# DDS_Tone_Shield.net
KiCad netlist of a schematic drawn in EAGLE
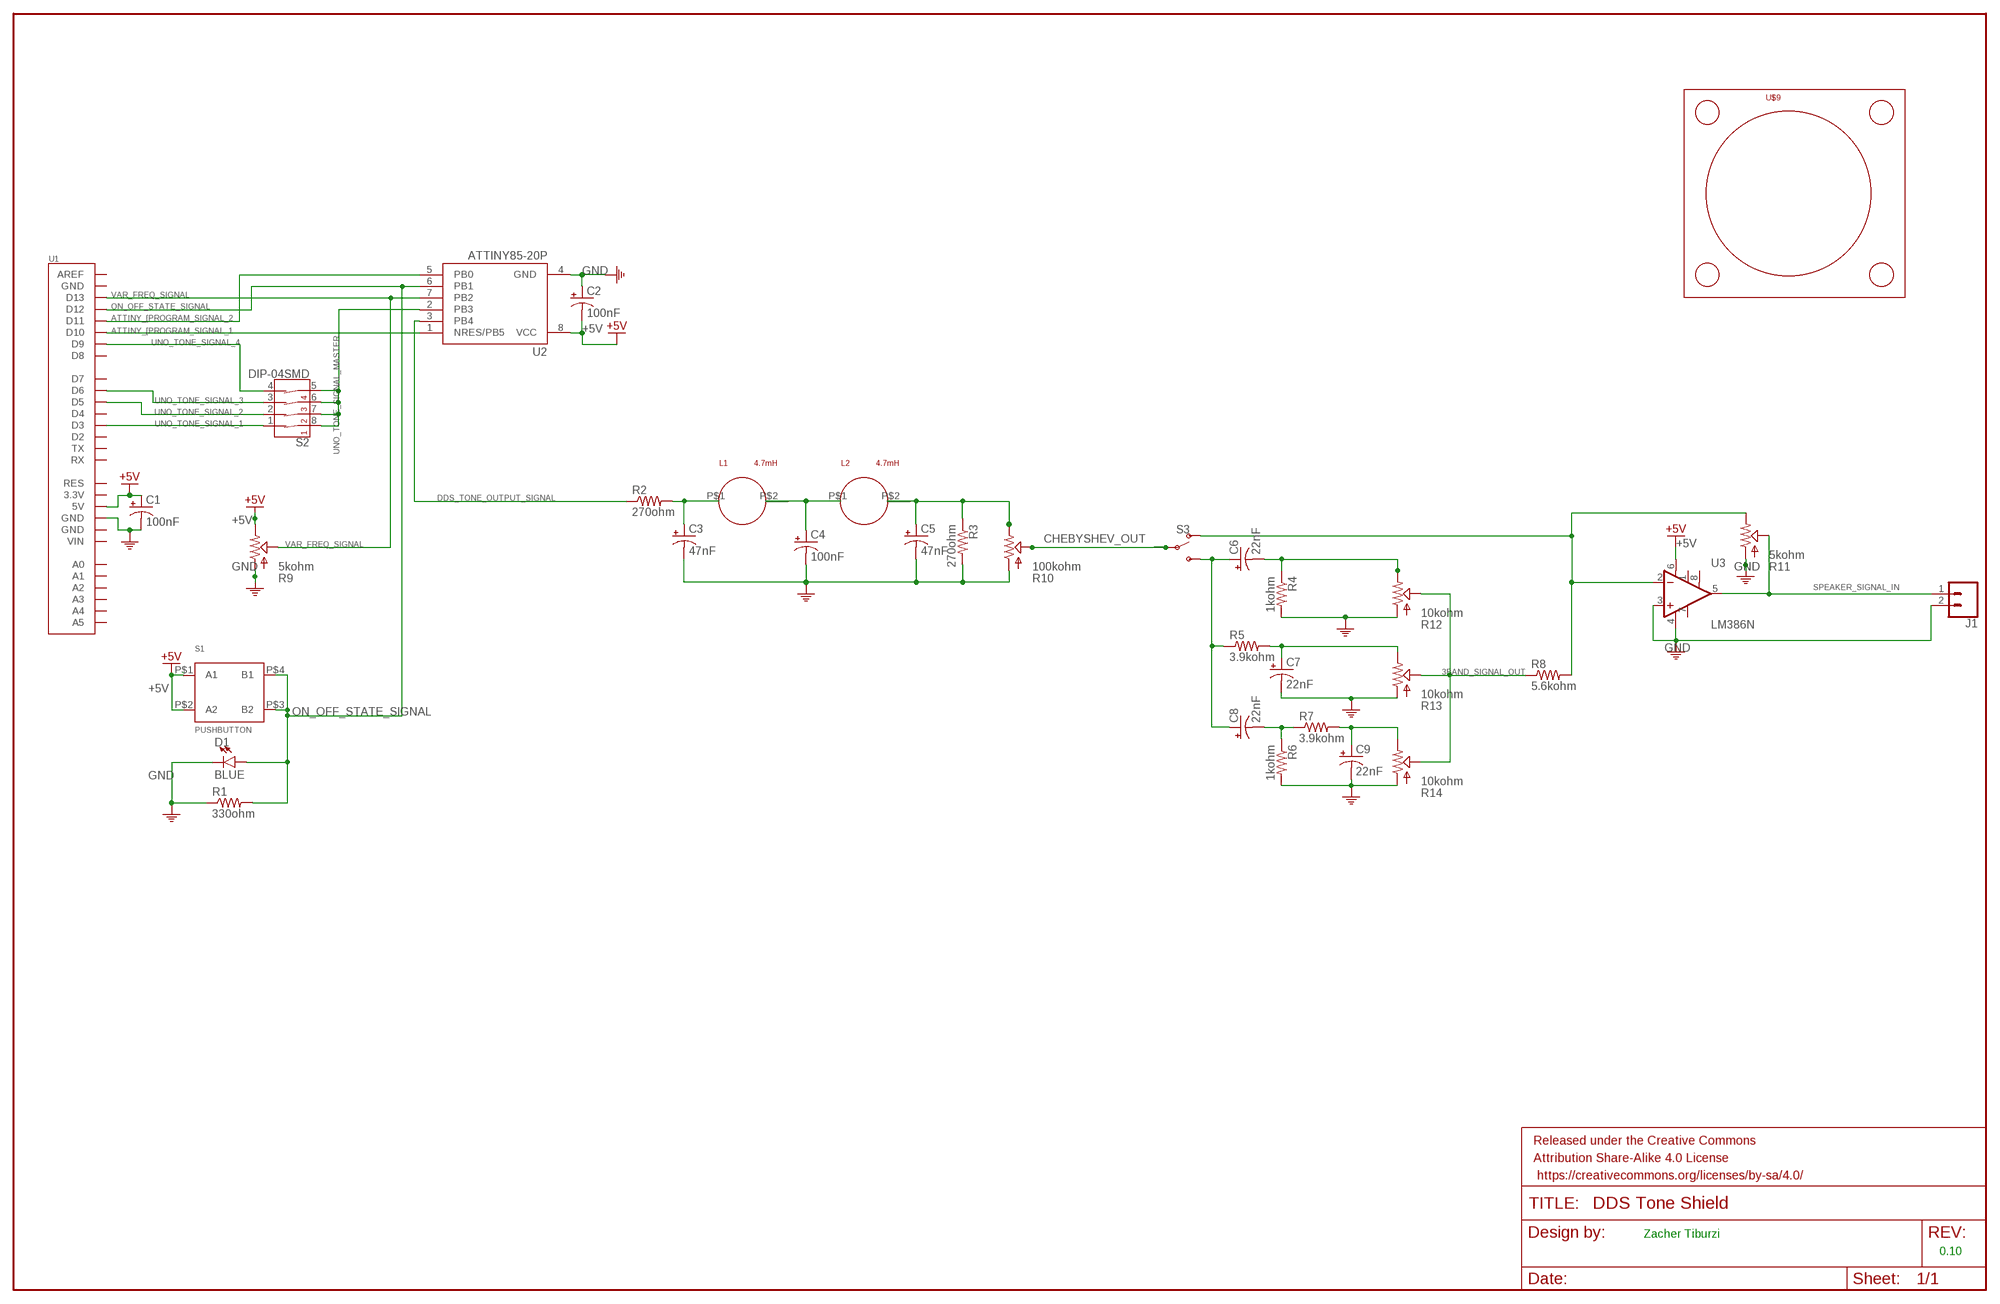
[diagram p0: schematic, sheet 1]

(export (version "E")
  (design (tool "Eeschema 10.0.6"))
  (components
    (comp (ref "C1")
      (value "100nF")
      (footprint "eagle-import:EIA3216")
      (libsource (lib "eagle-import") (part "CAP_POL1206"))
    )
    (comp (ref "C2")
      (value "100nF")
      (footprint "eagle-import:EIA3216")
      (libsource (lib "eagle-import") (part "CAP_POL1206"))
    )
    (comp (ref "C3")
      (value "47nF")
      (footprint "eagle-import:EIA3216")
      (libsource (lib "eagle-import") (part "CAP_POL1206"))
    )
    (comp (ref "C4")
      (value "100nF")
      (footprint "eagle-import:EIA3216")
      (libsource (lib "eagle-import") (part "CAP_POL1206"))
    )
    (comp (ref "C5")
      (value "47nF")
      (footprint "eagle-import:EIA3216")
      (libsource (lib "eagle-import") (part "CAP_POL1206"))
    )
    (comp (ref "C6")
      (value "22nF")
      (footprint "eagle-import:EIA3216")
      (libsource (lib "eagle-import") (part "CAP_POL1206"))
    )
    (comp (ref "C7")
      (value "22nF")
      (footprint "eagle-import:EIA3216")
      (libsource (lib "eagle-import") (part "CAP_POL1206"))
    )
    (comp (ref "C8")
      (value "22nF")
      (footprint "eagle-import:EIA3216")
      (libsource (lib "eagle-import") (part "CAP_POL1206"))
    )
    (comp (ref "C9")
      (value "22nF")
      (footprint "eagle-import:EIA3216")
      (libsource (lib "eagle-import") (part "CAP_POL1206"))
    )
    (comp (ref "D1")
      (value "BLUE")
      (footprint "eagle-import:LED-1206")
      (libsource (lib "eagle-import") (part "LED-BLUE1206"))
    )
    (comp (ref "FRAME2")
      (value "FRAME-LEDGER")
      (footprint "eagle-import:CREATIVE_COMMONS")
      (libsource (lib "eagle-import") (part "FRAME-LEDGER"))
    )
    (comp (ref "J1")
      (value "CONN_02")
      (footprint "eagle-import:1X02")
      (libsource (lib "eagle-import") (part "CONN_02"))
    )
    (comp (ref "L1")
      (value "4.7mH")
      (footprint "eagle-import:SDR0503-472JL")
      (libsource (lib "eagle-import") (part "INDUCTOR"))
    )
    (comp (ref "L2")
      (value "4.7mH")
      (footprint "eagle-import:SDR0503-472JL")
      (libsource (lib "eagle-import") (part "INDUCTOR"))
    )
    (comp (ref "R1")
      (value "330ohm")
      (footprint "eagle-import:1206")
      (libsource (lib "eagle-import") (part "RESISTOR1206"))
    )
    (comp (ref "R2")
      (value "270ohm")
      (footprint "eagle-import:1206")
      (libsource (lib "eagle-import") (part "RESISTOR1206"))
    )
    (comp (ref "R3")
      (value "270ohm")
      (footprint "eagle-import:1206")
      (libsource (lib "eagle-import") (part "RESISTOR1206"))
    )
    (comp (ref "R4")
      (value "1kohm")
      (footprint "eagle-import:1206")
      (libsource (lib "eagle-import") (part "RESISTOR1206"))
    )
    (comp (ref "R5")
      (value "3.9kohm")
      (footprint "eagle-import:1206")
      (libsource (lib "eagle-import") (part "RESISTOR1206"))
    )
    (comp (ref "R6")
      (value "1kohm")
      (footprint "eagle-import:1206")
      (libsource (lib "eagle-import") (part "RESISTOR1206"))
    )
    (comp (ref "R7")
      (value "3.9kohm")
      (footprint "eagle-import:1206")
      (libsource (lib "eagle-import") (part "RESISTOR1206"))
    )
    (comp (ref "R8")
      (value "5.6kohm")
      (footprint "eagle-import:1206")
      (libsource (lib "eagle-import") (part "RESISTOR1206"))
    )
    (comp (ref "R9")
      (value "5kohm")
      (footprint "eagle-import:RK09K_RK09D_SERIES")
      (libsource (lib "eagle-import") (part "POT1"))
    )
    (comp (ref "R10")
      (value "100kohm")
      (footprint "eagle-import:5150500311")
      (libsource (lib "eagle-import") (part "POT2"))
    )
    (comp (ref "R11")
      (value "5kohm")
      (footprint "eagle-import:RK09K_RK09D_SERIES")
      (libsource (lib "eagle-import") (part "POT1"))
    )
    (comp (ref "R12")
      (value "10kohm")
      (footprint "eagle-import:RK09K_RK09D_SERIES")
      (libsource (lib "eagle-import") (part "POT1"))
    )
    (comp (ref "R13")
      (value "10kohm")
      (footprint "eagle-import:RK09K_RK09D_SERIES")
      (libsource (lib "eagle-import") (part "POT1"))
    )
    (comp (ref "R14")
      (value "10kohm")
      (footprint "eagle-import:RK09K_RK09D_SERIES")
      (libsource (lib "eagle-import") (part "POT1"))
    )
    (comp (ref "S1")
      (value "PUSHBUTTON")
      (footprint "eagle-import:3CSH9_MEC_PUSHBUTTON")
      (libsource (lib "eagle-import") (part "PUSHBUTTON"))
    )
    (comp (ref "S2")
      (value "DIP-04SMD")
      (footprint "eagle-import:DIPSWITCH-04-SMD")
      (libsource (lib "eagle-import") (part "DIP-04SMD"))
    )
    (comp (ref "S3")
      (value "SWITCH-SPDT")
      (footprint "eagle-import:JS102011SAQN")
      (libsource (lib "eagle-import") (part "SWITCH-SPDT"))
    )
    (comp (ref "U$9")
      (value "SPEAKER")
      (footprint "eagle-import:CSS-40408N")
      (libsource (lib "eagle-import") (part "SPEAKER"))
    )
    (comp (ref "U1")
      (value "ARDUINO_SHIELD")
      (footprint "eagle-import:DUEMILANOVE_SHIELD")
      (libsource (lib "eagle-import") (part "ARDUINO_SHIELD"))
    )
    (comp (ref "U2")
      (value "ATTINY85-20P")
      (footprint "eagle-import:PDIP08_300MIL")
      (libsource (lib "eagle-import") (part "ATTINY85P-20"))
    )
    (comp (ref "U3")
      (value "LM386N")
      (footprint "eagle-import:DIP08")
      (libsource (lib "eagle-import") (part "LM386"))
    )
  )
  (nets
    (net (code "1") (name "+5V") (class "Default")
      (node (ref "C1") (pin "A") (pinfunction "+_A") (pintype "passive"))
      (node (ref "C2") (pin "C") (pinfunction "-_C") (pintype "passive"))
      (node (ref "R9") (pin "P$3") (pinfunction "E_P$3") (pintype "passive"))
      (node (ref "S1") (pin "P$1") (pinfunction "A1_P$1") (pintype "bidirectional"))
      (node (ref "S1") (pin "P$2") (pinfunction "A2_P$2") (pintype "bidirectional"))
      (node (ref "U1") (pin "5V") (pinfunction "5V_5V") (pintype "bidirectional"))
      (node (ref "U2") (pin "8") (pinfunction "VCC_8") (pintype "power_in"))
      (node (ref "U3") (pin "6") (pinfunction "V+_6") (pintype "power_in"))
    )
    (net (code "2") (name "/3BAND_SIGNAL_OUT") (class "Default")
      (node (ref "R12") (pin "P$2") (pinfunction "S_P$2") (pintype "passive"))
      (node (ref "R13") (pin "P$2") (pinfunction "S_P$2") (pintype "passive"))
      (node (ref "R14") (pin "P$2") (pinfunction "S_P$2") (pintype "passive"))
      (node (ref "R8") (pin "1") (pinfunction "1_1") (pintype "passive"))
    )
    (net (code "3") (name "/ATTINY_[PROGRAM_SIGNAL_1") (class "Default")
      (node (ref "U1") (pin "D10") (pinfunction "D10_D10") (pintype "bidirectional"))
      (node (ref "U2") (pin "1") (pinfunction "NRES/PB5_1") (pintype "bidirectional"))
    )
    (net (code "4") (name "/ATTINY_[PROGRAM_SIGNAL_2") (class "Default")
      (node (ref "U1") (pin "D11") (pinfunction "D11_D11") (pintype "bidirectional"))
      (node (ref "U2") (pin "5") (pinfunction "PB0_5") (pintype "bidirectional"))
    )
    (net (code "5") (name "/CHEBYSHEV_OUT") (class "Default")
      (node (ref "R10") (pin "P$20") (pinfunction "S_P$20") (pintype "passive"))
      (node (ref "S3") (pin "P$3") (pinfunction "P_P$3") (pintype "passive"))
    )
    (net (code "6") (name "/DDS_TONE_OUTPUT_SIGNAL") (class "Default")
      (node (ref "R2") (pin "1") (pinfunction "1_1") (pintype "passive"))
      (node (ref "U2") (pin "3") (pinfunction "PB4_3") (pintype "bidirectional"))
    )
    (net (code "7") (name "/ON_OFF_STATE_SIGNAL") (class "Default")
      (node (ref "D1") (pin "A") (pinfunction "A_A") (pintype "passive"))
      (node (ref "R1") (pin "2") (pinfunction "2_2") (pintype "passive"))
      (node (ref "S1") (pin "P$3") (pinfunction "B2_P$3") (pintype "bidirectional"))
      (node (ref "S1") (pin "P$4") (pinfunction "B1_P$4") (pintype "bidirectional"))
      (node (ref "U1") (pin "D12") (pinfunction "D12_D12") (pintype "bidirectional"))
      (node (ref "U2") (pin "6") (pinfunction "PB1_6") (pintype "bidirectional"))
    )
    (net (code "8") (name "/SPEAKER_SIGNAL_IN") (class "Default")
      (node (ref "J1") (pin "1") (pinfunction "1_1") (pintype "passive"))
      (node (ref "R11") (pin "P$2") (pinfunction "S_P$2") (pintype "passive"))
      (node (ref "U3") (pin "5") (pinfunction "OUT_5") (pintype "output"))
    )
    (net (code "9") (name "/UNO_TONE_SIGNAL_1") (class "Default")
      (node (ref "S2") (pin "1") (pinfunction "1A_1") (pintype "bidirectional"))
      (node (ref "U1") (pin "D3") (pinfunction "D3_D3") (pintype "bidirectional"))
    )
    (net (code "10") (name "/UNO_TONE_SIGNAL_2") (class "Default")
      (node (ref "S2") (pin "2") (pinfunction "2A_2") (pintype "bidirectional"))
      (node (ref "U1") (pin "D5") (pinfunction "D5_D5") (pintype "bidirectional"))
    )
    (net (code "11") (name "/UNO_TONE_SIGNAL_3") (class "Default")
      (node (ref "S2") (pin "3") (pinfunction "3A_3") (pintype "bidirectional"))
      (node (ref "U1") (pin "D6") (pinfunction "D6_D6") (pintype "bidirectional"))
    )
    (net (code "12") (name "/UNO_TONE_SIGNAL_4") (class "Default")
      (node (ref "S2") (pin "4") (pinfunction "4A_4") (pintype "bidirectional"))
      (node (ref "U1") (pin "D9") (pinfunction "D9_D9") (pintype "bidirectional"))
    )
    (net (code "13") (name "/UNO_TONE_SIGNAL_MASTER") (class "Default")
      (node (ref "S2") (pin "5") (pinfunction "4B_5") (pintype "bidirectional"))
      (node (ref "S2") (pin "6") (pinfunction "3B_6") (pintype "bidirectional"))
      (node (ref "S2") (pin "7") (pinfunction "2B_7") (pintype "bidirectional"))
      (node (ref "S2") (pin "8") (pinfunction "1B_8") (pintype "bidirectional"))
      (node (ref "U2") (pin "2") (pinfunction "PB3_2") (pintype "bidirectional"))
    )
    (net (code "14") (name "/VAR_FREQ_SIGNAL") (class "Default")
      (node (ref "R9") (pin "P$2") (pinfunction "S_P$2") (pintype "passive"))
      (node (ref "U1") (pin "D13") (pinfunction "D13_D13") (pintype "bidirectional"))
      (node (ref "U2") (pin "7") (pinfunction "PB2_7") (pintype "bidirectional"))
    )
    (net (code "15") (name "GND_US") (class "Default")
      (node (ref "C1") (pin "C") (pinfunction "-_C") (pintype "passive"))
      (node (ref "C2") (pin "A") (pinfunction "+_A") (pintype "passive"))
      (node (ref "C3") (pin "C") (pinfunction "-_C") (pintype "passive"))
      (node (ref "C4") (pin "C") (pinfunction "-_C") (pintype "passive"))
      (node (ref "C5") (pin "C") (pinfunction "-_C") (pintype "passive"))
      (node (ref "C7") (pin "C") (pinfunction "-_C") (pintype "passive"))
      (node (ref "C9") (pin "C") (pinfunction "-_C") (pintype "passive"))
      (node (ref "D1") (pin "C") (pinfunction "C_C") (pintype "passive"))
      (node (ref "J1") (pin "2") (pinfunction "2_2") (pintype "passive"))
      (node (ref "R1") (pin "1") (pinfunction "1_1") (pintype "passive"))
      (node (ref "R10") (pin "P$10") (pinfunction "A_P$10") (pintype "passive"))
      (node (ref "R11") (pin "P$1") (pinfunction "A_P$1") (pintype "passive"))
      (node (ref "R12") (pin "P$1") (pinfunction "A_P$1") (pintype "passive"))
      (node (ref "R13") (pin "P$1") (pinfunction "A_P$1") (pintype "passive"))
      (node (ref "R14") (pin "P$1") (pinfunction "A_P$1") (pintype "passive"))
      (node (ref "R3") (pin "2") (pinfunction "2_2") (pintype "passive"))
      (node (ref "R4") (pin "2") (pinfunction "2_2") (pintype "passive"))
      (node (ref "R6") (pin "2") (pinfunction "2_2") (pintype "passive"))
      (node (ref "R9") (pin "P$1") (pinfunction "A_P$1") (pintype "passive"))
      (node (ref "U1") (pin "GND@1") (pinfunction "GND_GND@1") (pintype "bidirectional"))
      (node (ref "U2") (pin "4") (pinfunction "GND_4") (pintype "power_in"))
      (node (ref "U3") (pin "3") (pinfunction "+IN_3") (pintype "input"))
      (node (ref "U3") (pin "4") (pinfunction "V-_4") (pintype "power_in"))
    )
    (net (code "16") (name "Net-(C3-+)") (class "Default")
      (node (ref "C3") (pin "A") (pinfunction "+_A") (pintype "passive"))
      (node (ref "L1") (pin "P$1") (pinfunction "P$1_P$1") (pintype "bidirectional"))
      (node (ref "R2") (pin "2") (pinfunction "2_2") (pintype "passive"))
    )
    (net (code "17") (name "Net-(C4-+)") (class "Default")
      (node (ref "C4") (pin "A") (pinfunction "+_A") (pintype "passive"))
      (node (ref "L1") (pin "P$2") (pinfunction "P$2_P$2") (pintype "bidirectional"))
      (node (ref "L2") (pin "P$1") (pinfunction "P$1_P$1") (pintype "bidirectional"))
    )
    (net (code "18") (name "Net-(C5-+)") (class "Default")
      (node (ref "C5") (pin "A") (pinfunction "+_A") (pintype "passive"))
      (node (ref "L2") (pin "P$2") (pinfunction "P$2_P$2") (pintype "bidirectional"))
      (node (ref "R10") (pin "P$30") (pinfunction "E_P$30") (pintype "passive"))
      (node (ref "R3") (pin "1") (pinfunction "1_1") (pintype "passive"))
    )
    (net (code "19") (name "Net-(C6-+)") (class "Default")
      (node (ref "C6") (pin "A") (pinfunction "+_A") (pintype "passive"))
      (node (ref "C8") (pin "A") (pinfunction "+_A") (pintype "passive"))
      (node (ref "R5") (pin "1") (pinfunction "1_1") (pintype "passive"))
      (node (ref "S3") (pin "P$1") (pinfunction "S_P$1") (pintype "passive"))
    )
    (net (code "20") (name "Net-(C6--)") (class "Default")
      (node (ref "C6") (pin "C") (pinfunction "-_C") (pintype "passive"))
      (node (ref "R12") (pin "P$3") (pinfunction "E_P$3") (pintype "passive"))
      (node (ref "R4") (pin "1") (pinfunction "1_1") (pintype "passive"))
    )
    (net (code "21") (name "Net-(C7-+)") (class "Default")
      (node (ref "C7") (pin "A") (pinfunction "+_A") (pintype "passive"))
      (node (ref "R13") (pin "P$3") (pinfunction "E_P$3") (pintype "passive"))
      (node (ref "R5") (pin "2") (pinfunction "2_2") (pintype "passive"))
    )
    (net (code "22") (name "Net-(C8--)") (class "Default")
      (node (ref "C8") (pin "C") (pinfunction "-_C") (pintype "passive"))
      (node (ref "R6") (pin "1") (pinfunction "1_1") (pintype "passive"))
      (node (ref "R7") (pin "1") (pinfunction "1_1") (pintype "passive"))
    )
    (net (code "23") (name "Net-(C9-+)") (class "Default")
      (node (ref "C9") (pin "A") (pinfunction "+_A") (pintype "passive"))
      (node (ref "R14") (pin "P$3") (pinfunction "E_P$3") (pintype "passive"))
      (node (ref "R7") (pin "2") (pinfunction "2_2") (pintype "passive"))
    )
    (net (code "24") (name "Net-(R11-E)") (class "Default")
      (node (ref "R11") (pin "P$3") (pinfunction "E_P$3") (pintype "passive"))
      (node (ref "R8") (pin "2") (pinfunction "2_2") (pintype "passive"))
      (node (ref "S3") (pin "P$2") (pinfunction "O_P$2") (pintype "passive"))
      (node (ref "U3") (pin "2") (pinfunction "-IN_2") (pintype "input"))
    )
    (net (code "25") (name "unconnected-(U1-GND-PadGND@0)") (class "Default")
      (node (ref "U1") (pin "GND@0") (pinfunction "GND_GND@0") (pintype "bidirectional"))
    )
    (net (code "26") (name "unconnected-(U1-GND-PadGND@2)") (class "Default")
      (node (ref "U1") (pin "GND@2") (pinfunction "GND_GND@2") (pintype "bidirectional"))
    )
    (net (code "27") (name "unconnected-(U1-Pad3.3V)") (class "Default")
      (node (ref "U1") (pin "3.3V") (pinfunction "3.3V_3.3V") (pintype "bidirectional"))
    )
    (net (code "28") (name "unconnected-(U1-PadA0)") (class "Default")
      (node (ref "U1") (pin "A0") (pinfunction "A0_A0") (pintype "bidirectional"))
    )
    (net (code "29") (name "unconnected-(U1-PadA1)") (class "Default")
      (node (ref "U1") (pin "A1") (pinfunction "A1_A1") (pintype "bidirectional"))
    )
    (net (code "30") (name "unconnected-(U1-PadA2)") (class "Default")
      (node (ref "U1") (pin "A2") (pinfunction "A2_A2") (pintype "bidirectional"))
    )
    (net (code "31") (name "unconnected-(U1-PadA3)") (class "Default")
      (node (ref "U1") (pin "A3") (pinfunction "A3_A3") (pintype "bidirectional"))
    )
    (net (code "32") (name "unconnected-(U1-PadA4)") (class "Default")
      (node (ref "U1") (pin "A4") (pinfunction "A4_A4") (pintype "bidirectional"))
    )
    (net (code "33") (name "unconnected-(U1-PadA5)") (class "Default")
      (node (ref "U1") (pin "A5") (pinfunction "A5_A5") (pintype "bidirectional"))
    )
    (net (code "34") (name "unconnected-(U1-PadAREF)") (class "Default")
      (node (ref "U1") (pin "AREF") (pinfunction "AREF_AREF") (pintype "bidirectional"))
    )
    (net (code "35") (name "unconnected-(U1-PadD2)") (class "Default")
      (node (ref "U1") (pin "D2") (pinfunction "D2_D2") (pintype "bidirectional"))
    )
    (net (code "36") (name "unconnected-(U1-PadD4)") (class "Default")
      (node (ref "U1") (pin "D4") (pinfunction "D4_D4") (pintype "bidirectional"))
    )
    (net (code "37") (name "unconnected-(U1-PadD7)") (class "Default")
      (node (ref "U1") (pin "D7") (pinfunction "D7_D7") (pintype "bidirectional"))
    )
    (net (code "38") (name "unconnected-(U1-PadD8)") (class "Default")
      (node (ref "U1") (pin "D8") (pinfunction "D8_D8") (pintype "bidirectional"))
    )
    (net (code "39") (name "unconnected-(U1-PadRES)") (class "Default")
      (node (ref "U1") (pin "RES") (pinfunction "RES_RES") (pintype "bidirectional"))
    )
    (net (code "40") (name "unconnected-(U1-PadRX)") (class "Default")
      (node (ref "U1") (pin "RX") (pinfunction "RX_RX") (pintype "bidirectional"))
    )
    (net (code "41") (name "unconnected-(U1-PadTX)") (class "Default")
      (node (ref "U1") (pin "TX") (pinfunction "TX_TX") (pintype "bidirectional"))
    )
    (net (code "42") (name "unconnected-(U1-PadVIN)") (class "Default")
      (node (ref "U1") (pin "VIN") (pinfunction "VIN_VIN") (pintype "bidirectional"))
    )
    (net (code "43") (name "unconnected-(U3-BP-Pad7)") (class "Default")
      (node (ref "U3") (pin "7") (pinfunction "BP_7") (pintype "bidirectional"))
    )
    (net (code "44") (name "unconnected-(U3-GAIN-Pad1)") (class "Default")
      (node (ref "U3") (pin "1") (pinfunction "GAIN_1") (pintype "bidirectional"))
    )
    (net (code "45") (name "unconnected-(U3-GAIN-Pad8)") (class "Default")
      (node (ref "U3") (pin "8") (pinfunction "GAIN_8") (pintype "bidirectional"))
    )
  )
)
